# Temperature_Card.net
KiCad netlist of a schematic drawn in EAGLE
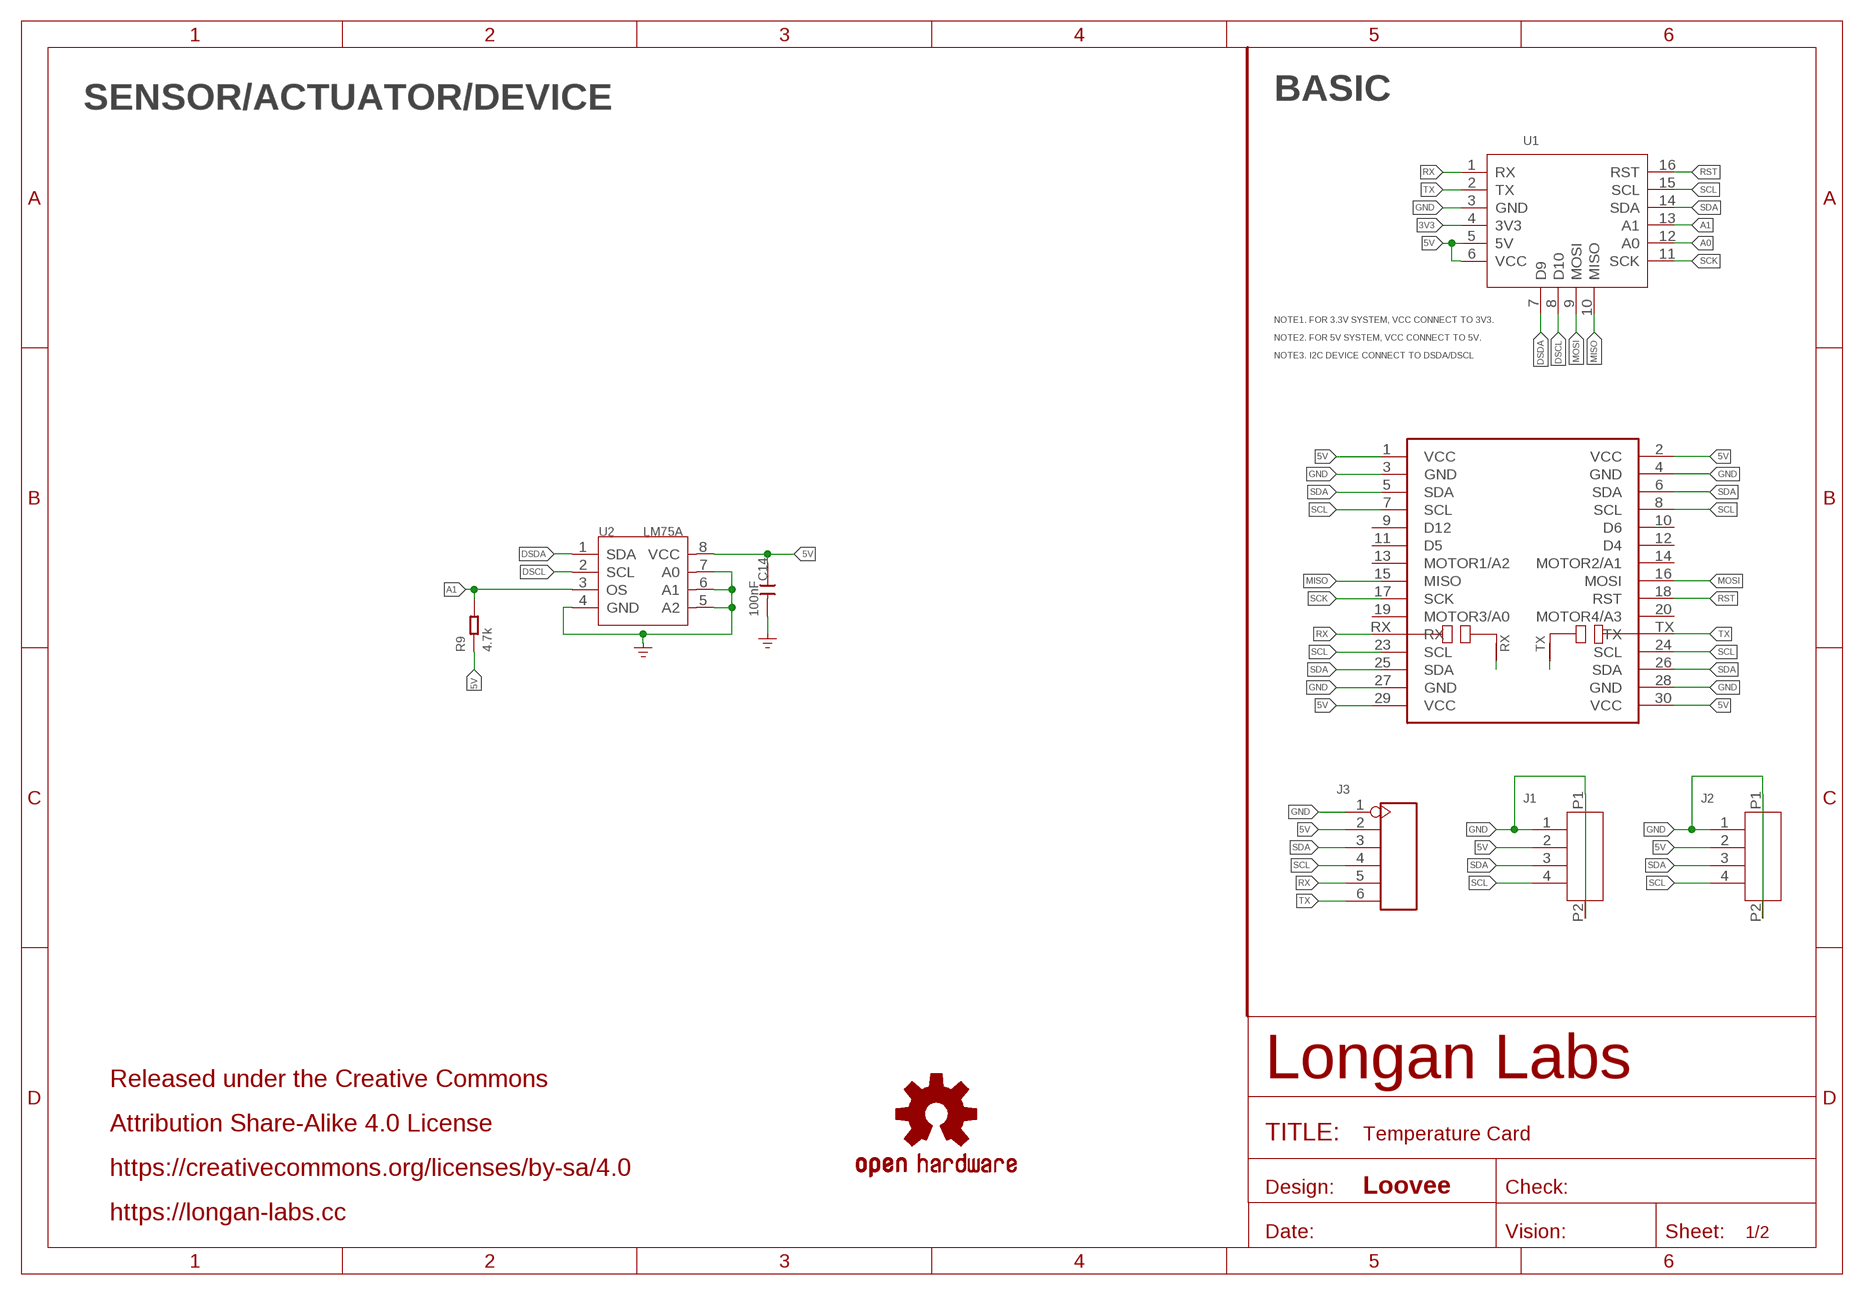
[diagram p0: schematic, sheet 1]

(export (version "E")
  (design (tool "Eeschema 10.0.6"))
  (components
    (comp (ref "C14")
      (value "100nF")
      (footprint "eagle-import:C0603")
      (libsource (lib "eagle-import") (part "CAP-0603"))
    )
    (comp (ref "J1")
      (value "HEADER-4P-1.0")
      (footprint "eagle-import:4P-1.0-90D")
      (libsource (lib "eagle-import") (part "HEADER-4P-1.0"))
    )
    (comp (ref "J2")
      (value "HEADER-4P-1.0")
      (footprint "eagle-import:4P-1.0-90D")
      (libsource (lib "eagle-import") (part "HEADER-4P-1.0"))
    )
    (comp (ref "J3")
      (value "HEADER-6P-55/35MIL")
      (footprint "eagle-import:H6-2.54")
      (libsource (lib "eagle-import") (part "HEADER-6P-55/35MIL"))
    )
    (comp (ref "LOGO2")
      (value "OSHW-LOGOS")
      (footprint "eagle-import:OSHW-LOGO-S")
      (libsource (lib "eagle-import") (part "OSHW-LOGOS"))
    )
    (comp (ref "MOUDLE2")
      (value "MOUDLE-CARDS-UART'BOARD'")
      (footprint "eagle-import:MOUDLE-2X15P-UART")
      (libsource (lib "eagle-import") (part "MOUDLE-CARDS-UART'BOARD'"))
    )
    (comp (ref "R9")
      (value "4.7k")
      (footprint "eagle-import:R0603")
      (libsource (lib "eagle-import") (part "RES-0603"))
    )
    (comp (ref "U1")
      (value "MOUDLE-CARDS")
      (footprint "eagle-import:16P-2.0-CARDS")
      (libsource (lib "eagle-import") (part "MOUDLE-CARDS"))
    )
    (comp (ref "U2")
      (value "LM75A")
      (footprint "eagle-import:TSSOP8-0.65-3X3MM")
      (libsource (lib "eagle-import") (part "SENSOR-LM75A"))
    )
  )
  (nets
    (net (code "1") (name "3V3") (class "Default")
      (node (ref "U1") (pin "4") (pinfunction "3V3_4") (pintype "bidirectional"))
    )
    (net (code "2") (name "5V") (class "Default")
      (node (ref "C14") (pin "1") (pinfunction "1_1") (pintype "passive"))
      (node (ref "J1") (pin "2") (pinfunction "2_2") (pintype "bidirectional"))
      (node (ref "J2") (pin "2") (pinfunction "2_2") (pintype "bidirectional"))
      (node (ref "J3") (pin "2") (pinfunction "2_2") (pintype "bidirectional"))
      (node (ref "MOUDLE2") (pin "1") (pinfunction "VCC_1") (pintype "bidirectional"))
      (node (ref "MOUDLE2") (pin "2") (pinfunction "VCC_2") (pintype "bidirectional"))
      (node (ref "MOUDLE2") (pin "29") (pinfunction "VCC_29") (pintype "bidirectional"))
      (node (ref "MOUDLE2") (pin "30") (pinfunction "VCC_30") (pintype "bidirectional"))
      (node (ref "R9") (pin "1") (pinfunction "1_1") (pintype "passive"))
      (node (ref "U1") (pin "5") (pinfunction "5V_5") (pintype "bidirectional"))
      (node (ref "U1") (pin "6") (pinfunction "VCC_6") (pintype "bidirectional"))
      (node (ref "U2") (pin "8") (pinfunction "VCC_8") (pintype "bidirectional"))
    )
    (net (code "3") (name "A0") (class "Default")
      (node (ref "U1") (pin "12") (pinfunction "A0_12") (pintype "bidirectional"))
    )
    (net (code "4") (name "A1") (class "Default")
      (node (ref "R9") (pin "2") (pinfunction "2_2") (pintype "passive"))
      (node (ref "U1") (pin "13") (pinfunction "A1_13") (pintype "bidirectional"))
      (node (ref "U2") (pin "3") (pinfunction "OS_3") (pintype "bidirectional"))
    )
    (net (code "5") (name "DSCL") (class "Default")
      (node (ref "U1") (pin "8") (pinfunction "D10_8") (pintype "bidirectional"))
      (node (ref "U2") (pin "2") (pinfunction "SCL_2") (pintype "bidirectional"))
    )
    (net (code "6") (name "DSDA") (class "Default")
      (node (ref "U1") (pin "7") (pinfunction "D9_7") (pintype "bidirectional"))
      (node (ref "U2") (pin "1") (pinfunction "SDA_1") (pintype "bidirectional"))
    )
    (net (code "7") (name "GND") (class "Default")
      (node (ref "C14") (pin "2") (pinfunction "2_2") (pintype "passive"))
      (node (ref "J1") (pin "1") (pinfunction "1_1") (pintype "bidirectional"))
      (node (ref "J1") (pin "P1") (pinfunction "P1_P1") (pintype "bidirectional"))
      (node (ref "J1") (pin "P2") (pinfunction "P2_P2") (pintype "bidirectional"))
      (node (ref "J2") (pin "1") (pinfunction "1_1") (pintype "bidirectional"))
      (node (ref "J2") (pin "P1") (pinfunction "P1_P1") (pintype "bidirectional"))
      (node (ref "J2") (pin "P2") (pinfunction "P2_P2") (pintype "bidirectional"))
      (node (ref "J3") (pin "1") (pinfunction "1_1") (pintype "bidirectional"))
      (node (ref "MOUDLE2") (pin "27") (pinfunction "GND_27") (pintype "bidirectional"))
      (node (ref "MOUDLE2") (pin "28") (pinfunction "GND_28") (pintype "bidirectional"))
      (node (ref "MOUDLE2") (pin "3") (pinfunction "GND_3") (pintype "bidirectional"))
      (node (ref "MOUDLE2") (pin "4") (pinfunction "GND_4") (pintype "bidirectional"))
      (node (ref "U1") (pin "3") (pinfunction "GND_3") (pintype "bidirectional"))
      (node (ref "U2") (pin "4") (pinfunction "GND_4") (pintype "bidirectional"))
      (node (ref "U2") (pin "5") (pinfunction "A2_5") (pintype "bidirectional"))
      (node (ref "U2") (pin "6") (pinfunction "A1_6") (pintype "bidirectional"))
      (node (ref "U2") (pin "7") (pinfunction "A0_7") (pintype "bidirectional"))
    )
    (net (code "8") (name "MISO") (class "Default")
      (node (ref "MOUDLE2") (pin "15") (pinfunction "MISO_15") (pintype "bidirectional"))
      (node (ref "U1") (pin "10") (pinfunction "MISO_10") (pintype "bidirectional"))
    )
    (net (code "9") (name "MOSI") (class "Default")
      (node (ref "MOUDLE2") (pin "16") (pinfunction "MOSI_16") (pintype "bidirectional"))
      (node (ref "U1") (pin "9") (pinfunction "MOSI_9") (pintype "bidirectional"))
    )
    (net (code "10") (name "Net-(MOUDLE2-RX{slash}N-PadRX{slash}N1)") (class "Default")
      (node (ref "MOUDLE2") (pin "RX/N1") (pinfunction "RX/N_RX/N1") (pintype "bidirectional"))
      (node (ref "MOUDLE2") (pin "RX/N2") (pinfunction "RX/N_RX/N2") (pintype "bidirectional"))
    )
    (net (code "11") (name "Net-(MOUDLE2-TX{slash}N-PadTX{slash}N1)") (class "Default")
      (node (ref "MOUDLE2") (pin "TX/N1") (pinfunction "TX/N_TX/N1") (pintype "bidirectional"))
      (node (ref "MOUDLE2") (pin "TX/N2") (pinfunction "TX/N_TX/N2") (pintype "bidirectional"))
    )
    (net (code "12") (name "RST") (class "Default")
      (node (ref "MOUDLE2") (pin "18") (pinfunction "RST_18") (pintype "bidirectional"))
      (node (ref "U1") (pin "16") (pinfunction "RST_16") (pintype "bidirectional"))
    )
    (net (code "13") (name "RX") (class "Default")
      (node (ref "J3") (pin "5") (pinfunction "5_5") (pintype "bidirectional"))
      (node (ref "MOUDLE2") (pin "RX") (pinfunction "RX_RX") (pintype "bidirectional"))
      (node (ref "U1") (pin "1") (pinfunction "RX_1") (pintype "bidirectional"))
    )
    (net (code "14") (name "SCK") (class "Default")
      (node (ref "MOUDLE2") (pin "17") (pinfunction "SCK_17") (pintype "bidirectional"))
      (node (ref "U1") (pin "11") (pinfunction "SCK_11") (pintype "bidirectional"))
    )
    (net (code "15") (name "SCL") (class "Default")
      (node (ref "J1") (pin "4") (pinfunction "4_4") (pintype "bidirectional"))
      (node (ref "J2") (pin "4") (pinfunction "4_4") (pintype "bidirectional"))
      (node (ref "J3") (pin "4") (pinfunction "4_4") (pintype "bidirectional"))
      (node (ref "MOUDLE2") (pin "23") (pinfunction "SCL_23") (pintype "bidirectional"))
      (node (ref "MOUDLE2") (pin "24") (pinfunction "SCL_24") (pintype "bidirectional"))
      (node (ref "MOUDLE2") (pin "7") (pinfunction "SCL_7") (pintype "bidirectional"))
      (node (ref "MOUDLE2") (pin "8") (pinfunction "SCL_8") (pintype "bidirectional"))
      (node (ref "U1") (pin "15") (pinfunction "SCL_15") (pintype "bidirectional"))
    )
    (net (code "16") (name "SDA") (class "Default")
      (node (ref "J1") (pin "3") (pinfunction "3_3") (pintype "bidirectional"))
      (node (ref "J2") (pin "3") (pinfunction "3_3") (pintype "bidirectional"))
      (node (ref "J3") (pin "3") (pinfunction "3_3") (pintype "bidirectional"))
      (node (ref "MOUDLE2") (pin "25") (pinfunction "SDA_25") (pintype "bidirectional"))
      (node (ref "MOUDLE2") (pin "26") (pinfunction "SDA_26") (pintype "bidirectional"))
      (node (ref "MOUDLE2") (pin "5") (pinfunction "SDA_5") (pintype "bidirectional"))
      (node (ref "MOUDLE2") (pin "6") (pinfunction "SDA_6") (pintype "bidirectional"))
      (node (ref "U1") (pin "14") (pinfunction "SDA_14") (pintype "bidirectional"))
    )
    (net (code "17") (name "TX") (class "Default")
      (node (ref "J3") (pin "6") (pinfunction "6_6") (pintype "bidirectional"))
      (node (ref "MOUDLE2") (pin "TX") (pinfunction "TX_TX") (pintype "bidirectional"))
      (node (ref "U1") (pin "2") (pinfunction "TX_2") (pintype "bidirectional"))
    )
    (net (code "18") (name "unconnected-(MOUDLE2-D4-Pad12)") (class "Default")
      (node (ref "MOUDLE2") (pin "12") (pinfunction "D4_12") (pintype "bidirectional"))
    )
    (net (code "19") (name "unconnected-(MOUDLE2-D5-Pad11)") (class "Default")
      (node (ref "MOUDLE2") (pin "11") (pinfunction "D5_11") (pintype "bidirectional"))
    )
    (net (code "20") (name "unconnected-(MOUDLE2-D6-Pad10)") (class "Default")
      (node (ref "MOUDLE2") (pin "10") (pinfunction "D6_10") (pintype "bidirectional"))
    )
    (net (code "21") (name "unconnected-(MOUDLE2-D12-Pad9)") (class "Default")
      (node (ref "MOUDLE2") (pin "9") (pinfunction "D12_9") (pintype "bidirectional"))
    )
    (net (code "22") (name "unconnected-(MOUDLE2-MOTOR1{slash}A2-Pad13)") (class "Default")
      (node (ref "MOUDLE2") (pin "13") (pinfunction "MOTOR1/A2_13") (pintype "bidirectional"))
    )
    (net (code "23") (name "unconnected-(MOUDLE2-MOTOR2{slash}A1-Pad14)") (class "Default")
      (node (ref "MOUDLE2") (pin "14") (pinfunction "MOTOR2/A1_14") (pintype "bidirectional"))
    )
    (net (code "24") (name "unconnected-(MOUDLE2-MOTOR3{slash}A0-Pad19)") (class "Default")
      (node (ref "MOUDLE2") (pin "19") (pinfunction "MOTOR3/A0_19") (pintype "bidirectional"))
    )
    (net (code "25") (name "unconnected-(MOUDLE2-MOTOR4{slash}A3-Pad20)") (class "Default")
      (node (ref "MOUDLE2") (pin "20") (pinfunction "MOTOR4/A3_20") (pintype "bidirectional"))
    )
  )
)
